# MRCS-cpNode-Wemos.net
KiCad netlist of a schematic drawn in EAGLE
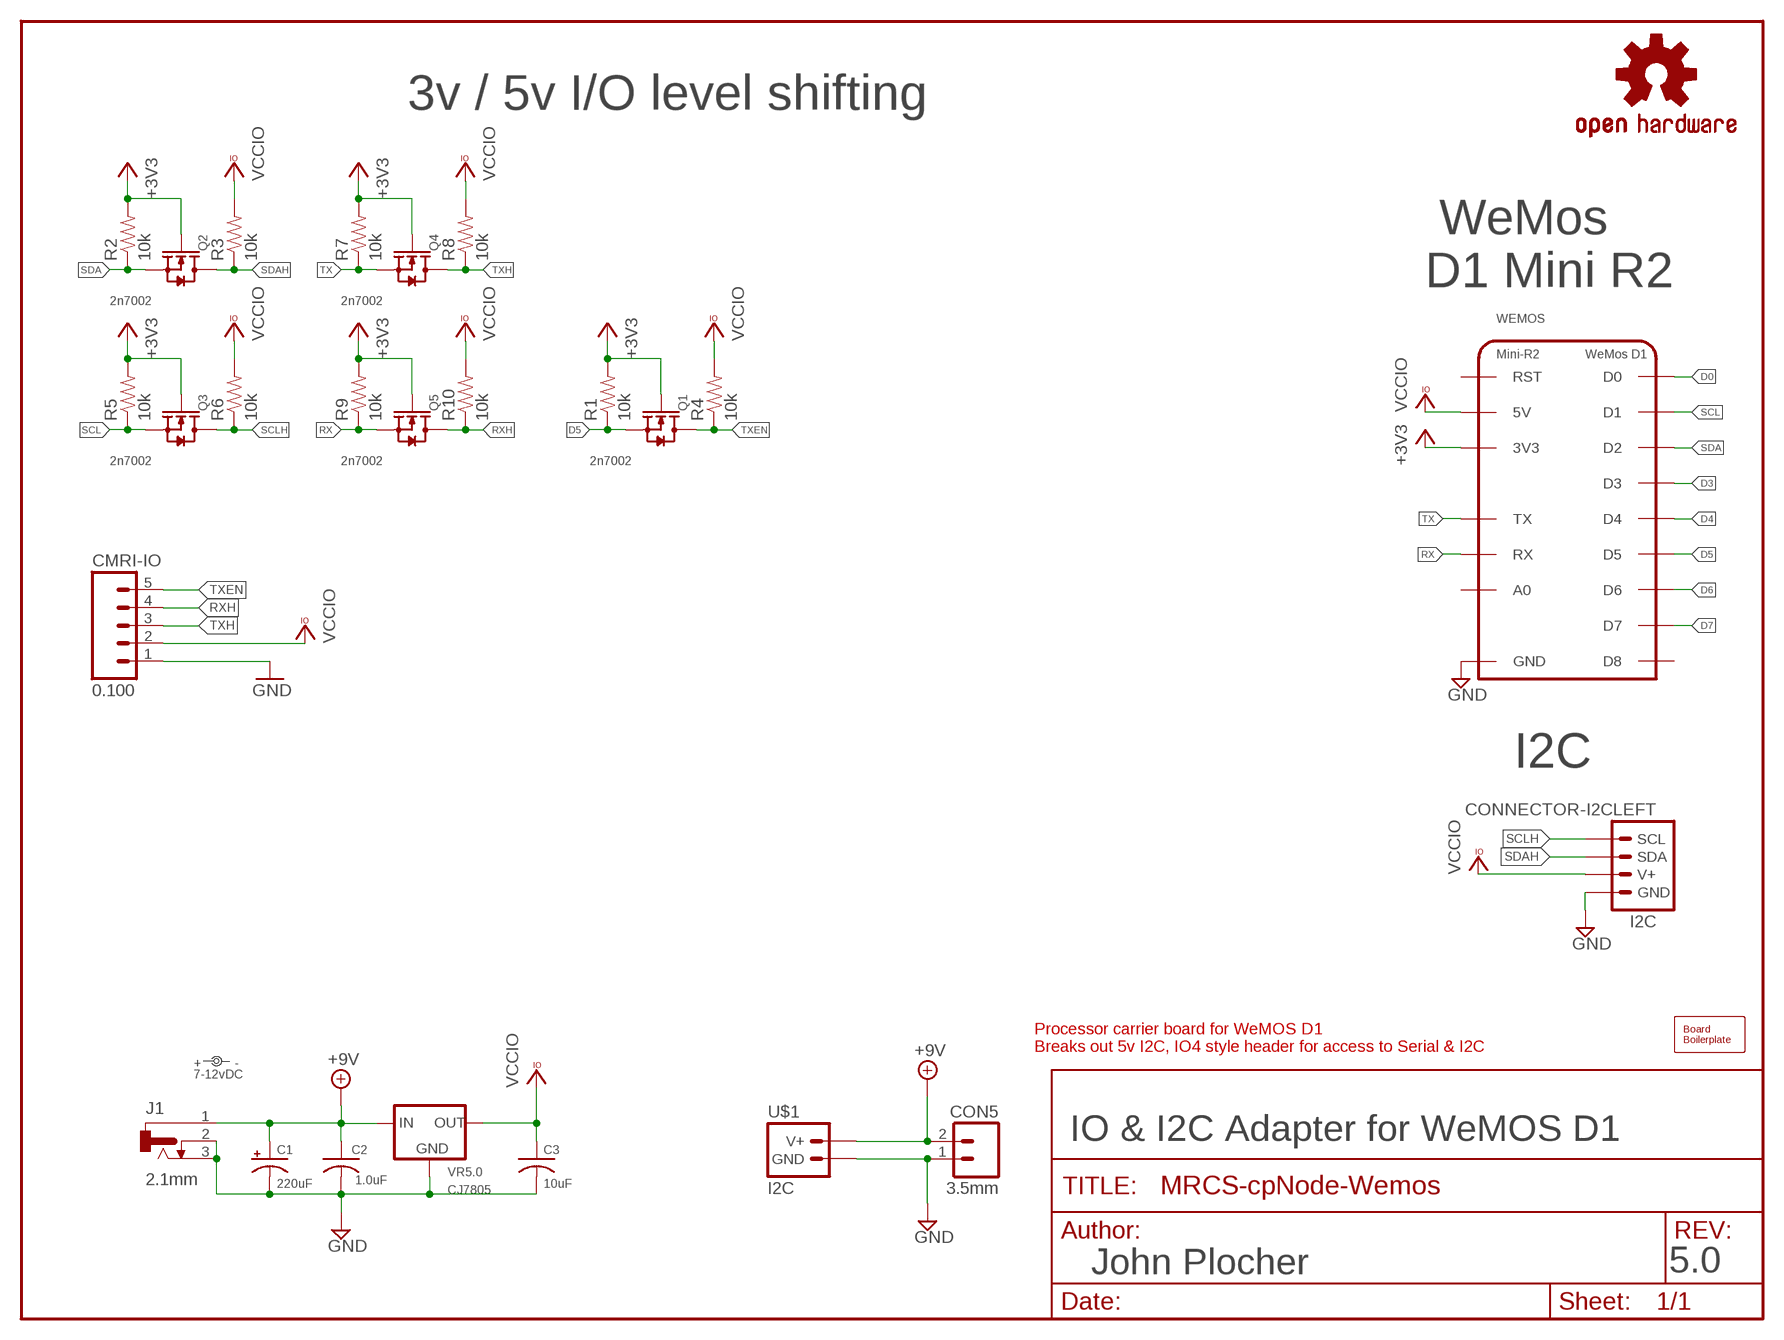
[diagram p0: schematic, sheet 1]

(export (version "E")
  (design (tool "Eeschema 10.0.6"))
  (components
    (comp (ref "BOARD")
      (value "BOARD")
      (footprint "eagle-import:BOARD-DINRAIL-2.7IN-8CM")
      (libsource (lib "eagle-import") (part "BOARD69X80"))
    )
    (comp (ref "C1")
      (value "220uF")
      (footprint "eagle-import:0810-CAP")
      (libsource (lib "eagle-import") (part "CAP-POL0810"))
    )
    (comp (ref "C2")
      (value "1.0uF")
      (footprint "eagle-import:0603-CAP")
      (libsource (lib "eagle-import") (part "CAP0603"))
    )
    (comp (ref "C3")
      (value "10uF")
      (footprint "eagle-import:0603-CAP")
      (libsource (lib "eagle-import") (part "CAP0603"))
    )
    (comp (ref "CMRI-IO")
      (value "0.100")
      (footprint "eagle-import:1X05_LOCK_LONGPADS")
      (libsource (lib "eagle-import") (part "CONNECTOR-M05LOCK_LONGPADS"))
    )
    (comp (ref "CON5")
      (value "3.5mm")
      (footprint "eagle-import:SCREWTERMINAL-3.5MM-2_LOCK")
      (libsource (lib "eagle-import") (part "CONNECTOR-M023.5MM-LOCK"))
    )
    (comp (ref "I2C")
      (value "CONNECTOR-I2CLEFT")
      (footprint "eagle-import:I2C-L")
      (libsource (lib "eagle-import") (part "CONNECTOR-I2CLEFT"))
    )
    (comp (ref "J1")
      (value "2.1mm")
      (footprint "eagle-import:DCJ0202")
      (libsource (lib "eagle-import") (part "CONNECTOR-DC-POWER-RA"))
    )
    (comp (ref "LABEL1")
      (value "7-12vDC")
      (footprint "eagle-import:PWR_LABEL")
      (libsource (lib "eagle-import") (part "DOC-POWER_LABEL"))
    )
    (comp (ref "OSHW1")
      (value "OSHW")
      (footprint "eagle-import:OSHW-LOGO-L")
      (libsource (lib "eagle-import") (part "OSHW-LOGOL"))
    )
    (comp (ref "Q1")
      (value "2n7002")
      (footprint "eagle-import:SOT23")
      (libsource (lib "eagle-import") (part "MOSFET-N--?SOT23BSS138"))
    )
    (comp (ref "Q2")
      (value "2n7002")
      (footprint "eagle-import:SOT23")
      (libsource (lib "eagle-import") (part "MOSFET-N--?SOT23BSS138"))
    )
    (comp (ref "Q3")
      (value "2n7002")
      (footprint "eagle-import:SOT23")
      (libsource (lib "eagle-import") (part "MOSFET-N--?SOT23BSS138"))
    )
    (comp (ref "Q4")
      (value "2n7002")
      (footprint "eagle-import:SOT23")
      (libsource (lib "eagle-import") (part "MOSFET-N--?SOT23BSS138"))
    )
    (comp (ref "Q5")
      (value "2n7002")
      (footprint "eagle-import:SOT23")
      (libsource (lib "eagle-import") (part "MOSFET-N--?SOT23BSS138"))
    )
    (comp (ref "R1")
      (value "10k")
      (footprint "eagle-import:0805-RES")
      (libsource (lib "eagle-import") (part "R0805-RES"))
    )
    (comp (ref "R2")
      (value "10k")
      (footprint "eagle-import:0603-RES")
      (libsource (lib "eagle-import") (part "R0603-RES"))
    )
    (comp (ref "R3")
      (value "10k")
      (footprint "eagle-import:0603-RES")
      (libsource (lib "eagle-import") (part "R0603-RES"))
    )
    (comp (ref "R4")
      (value "10k")
      (footprint "eagle-import:0603-RES")
      (libsource (lib "eagle-import") (part "R0603-RES"))
    )
    (comp (ref "R5")
      (value "10k")
      (footprint "eagle-import:0603-RES")
      (libsource (lib "eagle-import") (part "R0603-RES"))
    )
    (comp (ref "R6")
      (value "10k")
      (footprint "eagle-import:0603-RES")
      (libsource (lib "eagle-import") (part "R0603-RES"))
    )
    (comp (ref "R7")
      (value "10k")
      (footprint "eagle-import:0603-RES")
      (libsource (lib "eagle-import") (part "R0603-RES"))
    )
    (comp (ref "R8")
      (value "10k")
      (footprint "eagle-import:0603-RES")
      (libsource (lib "eagle-import") (part "R0603-RES"))
    )
    (comp (ref "R9")
      (value "10k")
      (footprint "eagle-import:0603-RES")
      (libsource (lib "eagle-import") (part "R0603-RES"))
    )
    (comp (ref "R10")
      (value "10k")
      (footprint "eagle-import:0603-RES")
      (libsource (lib "eagle-import") (part "R0603-RES"))
    )
    (comp (ref "U$1")
      (value "I2C")
      (footprint "eagle-import:POWER-R2")
      (libsource (lib "eagle-import") (part "CONNECTOR-POWER-L"))
    )
    (comp (ref "VR5.0")
      (value "CJ7805")
      (footprint "eagle-import:TO-252")
      (libsource (lib "eagle-import") (part "VREG-?-DPAK5"))
    )
    (comp (ref "WEMOS")
      (value "Mini-R2")
      (footprint "eagle-import:WEMOS-D1")
      (libsource (lib "eagle-import") (part "WEMOS-D1V1"))
    )
  )
  (nets
    (net (code "1") (name "+3V3") (class "Default")
      (node (ref "Q1") (pin "1") (pinfunction "G_1") (pintype "passive"))
      (node (ref "Q2") (pin "1") (pinfunction "G_1") (pintype "passive"))
      (node (ref "Q3") (pin "1") (pinfunction "G_1") (pintype "passive"))
      (node (ref "Q4") (pin "1") (pinfunction "G_1") (pintype "passive"))
      (node (ref "Q5") (pin "1") (pinfunction "G_1") (pintype "passive"))
      (node (ref "R1") (pin "2") (pinfunction "2_2") (pintype "passive"))
      (node (ref "R2") (pin "2") (pinfunction "2_2") (pintype "passive"))
      (node (ref "R5") (pin "2") (pinfunction "2_2") (pintype "passive"))
      (node (ref "R7") (pin "2") (pinfunction "2_2") (pintype "passive"))
      (node (ref "R9") (pin "2") (pinfunction "2_2") (pintype "passive"))
      (node (ref "WEMOS") (pin "3V3") (pinfunction "3V3_3V3") (pintype "bidirectional"))
    )
    (net (code "2") (name "+9V") (class "Default")
      (node (ref "C1") (pin "+") (pinfunction "+_+") (pintype "passive"))
      (node (ref "C2") (pin "1") (pinfunction "1_1") (pintype "passive"))
      (node (ref "CON5") (pin "2") (pinfunction "B_2") (pintype "passive"))
      (node (ref "J1") (pin "1") (pinfunction "1_1") (pintype "passive"))
      (node (ref "U$1") (pin "V+") (pinfunction "V+_V+") (pintype "passive"))
      (node (ref "U$1") (pin "V+@1") (pinfunction "V+_V+@1") (pintype "passive"))
      (node (ref "U$1") (pin "V+@2") (pinfunction "V+_V+@2") (pintype "passive"))
      (node (ref "U$1") (pin "V+@3") (pinfunction "V+_V+@3") (pintype "passive"))
      (node (ref "VR5.0") (pin "1") (pinfunction "IN_1") (pintype "input"))
    )
    (net (code "3") (name "D0") (class "Default")
      (node (ref "WEMOS") (pin "D0") (pinfunction "D0_D0") (pintype "bidirectional"))
    )
    (net (code "4") (name "D3") (class "Default")
      (node (ref "WEMOS") (pin "D3") (pinfunction "D3_D3") (pintype "bidirectional"))
    )
    (net (code "5") (name "D4") (class "Default")
      (node (ref "WEMOS") (pin "D4") (pinfunction "D4_D4") (pintype "bidirectional"))
    )
    (net (code "6") (name "D5") (class "Default")
      (node (ref "Q1") (pin "2") (pinfunction "S_2") (pintype "passive"))
      (node (ref "R1") (pin "1") (pinfunction "1_1") (pintype "passive"))
      (node (ref "WEMOS") (pin "D5") (pinfunction "D5_D5") (pintype "bidirectional"))
    )
    (net (code "7") (name "D6") (class "Default")
      (node (ref "WEMOS") (pin "D6") (pinfunction "D6_D6") (pintype "bidirectional"))
    )
    (net (code "8") (name "D7") (class "Default")
      (node (ref "WEMOS") (pin "D7") (pinfunction "D7_D7") (pintype "bidirectional"))
    )
    (net (code "9") (name "GND") (class "Default")
      (node (ref "C1") (pin "-") (pinfunction "-_-") (pintype "passive"))
      (node (ref "C2") (pin "2") (pinfunction "2_2") (pintype "passive"))
      (node (ref "C3") (pin "2") (pinfunction "2_2") (pintype "passive"))
      (node (ref "CMRI-IO") (pin "1") (pinfunction "1_1") (pintype "passive"))
      (node (ref "CON5") (pin "1") (pinfunction "A_1") (pintype "passive"))
      (node (ref "I2C") (pin "GND") (pinfunction "GND_GND") (pintype "passive"))
      (node (ref "I2C") (pin "GND@1") (pinfunction "GND_GND@1") (pintype "passive"))
      (node (ref "J1") (pin "2") (pinfunction "2_2") (pintype "passive"))
      (node (ref "J1") (pin "3") (pinfunction "3_3") (pintype "passive"))
      (node (ref "U$1") (pin "GND") (pinfunction "GND_GND") (pintype "passive"))
      (node (ref "U$1") (pin "GND@1") (pinfunction "GND_GND@1") (pintype "passive"))
      (node (ref "U$1") (pin "GND@2") (pinfunction "GND_GND@2") (pintype "passive"))
      (node (ref "U$1") (pin "GND@3") (pinfunction "GND_GND@3") (pintype "passive"))
      (node (ref "VR5.0") (pin "2") (pinfunction "GND_2") (pintype "input"))
      (node (ref "WEMOS") (pin "GND") (pinfunction "GND_GND") (pintype "bidirectional"))
    )
    (net (code "10") (name "RX") (class "Default")
      (node (ref "Q5") (pin "2") (pinfunction "S_2") (pintype "passive"))
      (node (ref "R9") (pin "1") (pinfunction "1_1") (pintype "passive"))
      (node (ref "WEMOS") (pin "RX") (pinfunction "RX_RX") (pintype "bidirectional"))
    )
    (net (code "11") (name "RXH") (class "Default")
      (node (ref "CMRI-IO") (pin "4") (pinfunction "4_4") (pintype "passive"))
      (node (ref "Q5") (pin "3") (pinfunction "D_3") (pintype "passive"))
      (node (ref "R10") (pin "1") (pinfunction "1_1") (pintype "passive"))
    )
    (net (code "12") (name "SCL") (class "Default")
      (node (ref "Q3") (pin "2") (pinfunction "S_2") (pintype "passive"))
      (node (ref "R5") (pin "1") (pinfunction "1_1") (pintype "passive"))
      (node (ref "WEMOS") (pin "D1") (pinfunction "D1_D1") (pintype "bidirectional"))
    )
    (net (code "13") (name "SCLH") (class "Default")
      (node (ref "I2C") (pin "SCL") (pinfunction "SCL_SCL") (pintype "passive"))
      (node (ref "I2C") (pin "SCL@1") (pinfunction "SCL_SCL@1") (pintype "passive"))
      (node (ref "Q3") (pin "3") (pinfunction "D_3") (pintype "passive"))
      (node (ref "R6") (pin "1") (pinfunction "1_1") (pintype "passive"))
    )
    (net (code "14") (name "SDA") (class "Default")
      (node (ref "Q2") (pin "2") (pinfunction "S_2") (pintype "passive"))
      (node (ref "R2") (pin "1") (pinfunction "1_1") (pintype "passive"))
      (node (ref "WEMOS") (pin "D2") (pinfunction "D2_D2") (pintype "bidirectional"))
    )
    (net (code "15") (name "SDAH") (class "Default")
      (node (ref "I2C") (pin "SDA") (pinfunction "SDA_SDA") (pintype "passive"))
      (node (ref "I2C") (pin "SDA@1") (pinfunction "SDA_SDA@1") (pintype "passive"))
      (node (ref "Q2") (pin "3") (pinfunction "D_3") (pintype "passive"))
      (node (ref "R3") (pin "1") (pinfunction "1_1") (pintype "passive"))
    )
    (net (code "16") (name "TX") (class "Default")
      (node (ref "Q4") (pin "2") (pinfunction "S_2") (pintype "passive"))
      (node (ref "R7") (pin "1") (pinfunction "1_1") (pintype "passive"))
      (node (ref "WEMOS") (pin "TX") (pinfunction "TX_TX") (pintype "bidirectional"))
    )
    (net (code "17") (name "TXEN") (class "Default")
      (node (ref "CMRI-IO") (pin "5") (pinfunction "5_5") (pintype "passive"))
      (node (ref "Q1") (pin "3") (pinfunction "D_3") (pintype "passive"))
      (node (ref "R4") (pin "1") (pinfunction "1_1") (pintype "passive"))
    )
    (net (code "18") (name "TXH") (class "Default")
      (node (ref "CMRI-IO") (pin "3") (pinfunction "3_3") (pintype "passive"))
      (node (ref "Q4") (pin "3") (pinfunction "D_3") (pintype "passive"))
      (node (ref "R8") (pin "1") (pinfunction "1_1") (pintype "passive"))
    )
    (net (code "19") (name "VCCIO") (class "Default")
      (node (ref "C3") (pin "1") (pinfunction "1_1") (pintype "passive"))
      (node (ref "CMRI-IO") (pin "2") (pinfunction "2_2") (pintype "passive"))
      (node (ref "I2C") (pin "V+") (pinfunction "V+_V+") (pintype "passive"))
      (node (ref "I2C") (pin "V+@1") (pinfunction "V+_V+@1") (pintype "passive"))
      (node (ref "R10") (pin "2") (pinfunction "2_2") (pintype "passive"))
      (node (ref "R3") (pin "2") (pinfunction "2_2") (pintype "passive"))
      (node (ref "R4") (pin "2") (pinfunction "2_2") (pintype "passive"))
      (node (ref "R6") (pin "2") (pinfunction "2_2") (pintype "passive"))
      (node (ref "R8") (pin "2") (pinfunction "2_2") (pintype "passive"))
      (node (ref "VR5.0") (pin "3") (pinfunction "OUT_3") (pintype "output"))
      (node (ref "WEMOS") (pin "5V") (pinfunction "5V_5V") (pintype "bidirectional"))
    )
    (net (code "20") (name "unconnected-(WEMOS-PadA0)") (class "Default")
      (node (ref "WEMOS") (pin "A0") (pinfunction "A0_A0") (pintype "bidirectional"))
    )
    (net (code "21") (name "unconnected-(WEMOS-PadD8)") (class "Default")
      (node (ref "WEMOS") (pin "D8") (pinfunction "D8_D8") (pintype "bidirectional"))
    )
    (net (code "22") (name "unconnected-(WEMOS-PadRST)") (class "Default")
      (node (ref "WEMOS") (pin "RST") (pinfunction "RST_RST") (pintype "bidirectional"))
    )
  )
)
